# FOC_Power.net
KiCad netlist of a schematic drawn in Altium Designer
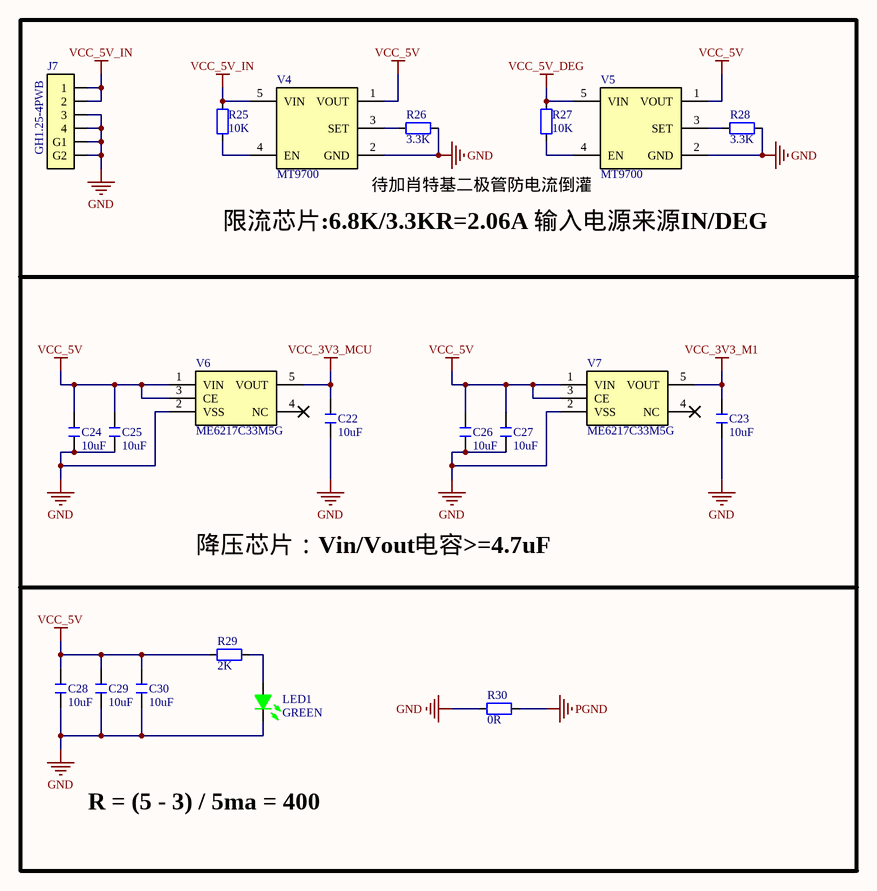
[diagram p0: FOC_Power.SchDoc]

(export (version "E")
  (design (tool "Eeschema 10.0.6"))
  (components
    (comp (ref "C22")
      (value "10uF")
      (footprint "C 0603_L")
      (description "贴片电容")
      (libsource (lib "0.1 电阻_电容_电感") (part "C"))
    )
    (comp (ref "C23")
      (value "10uF")
      (footprint "C 0603_L")
      (description "贴片电容")
      (libsource (lib "0.1 电阻_电容_电感") (part "C"))
    )
    (comp (ref "C24")
      (value "10uF")
      (footprint "C 0603_L")
      (description "贴片电容")
      (libsource (lib "0.1 电阻_电容_电感") (part "C"))
    )
    (comp (ref "C25")
      (value "10uF")
      (footprint "C 0603_L")
      (description "贴片电容")
      (libsource (lib "0.1 电阻_电容_电感") (part "C"))
    )
    (comp (ref "C26")
      (value "10uF")
      (footprint "C 0603_L")
      (description "贴片电容")
      (libsource (lib "0.1 电阻_电容_电感") (part "C"))
    )
    (comp (ref "C27")
      (value "10uF")
      (footprint "C 0603_L")
      (description "贴片电容")
      (libsource (lib "0.1 电阻_电容_电感") (part "C"))
    )
    (comp (ref "C28")
      (value "10uF")
      (footprint "C 0603_L")
      (description "贴片电容")
      (libsource (lib "0.1 电阻_电容_电感") (part "C"))
    )
    (comp (ref "C29")
      (value "10uF")
      (footprint "C 0603_L")
      (description "贴片电容")
      (libsource (lib "0.1 电阻_电容_电感") (part "C"))
    )
    (comp (ref "C30")
      (value "10uF")
      (footprint "C 0603_L")
      (description "贴片电容")
      (libsource (lib "0.1 电阻_电容_电感") (part "C"))
    )
    (comp (ref "J7")
      (value "GH1.25-4PWB")
      (footprint "GH1.25-4PWB")
      (description "GH1.25-4P 卧贴")
      (libsource (lib "3.5 连接器") (part "GH1.25-4PWB"))
    )
    (comp (ref "LED1")
      (value "GREEN")
      (footprint "LED_0603G")
      (description "贴片LED 0603 绿色")
      (libsource (lib "0.6 发光二极管") (part "LED_G"))
    )
    (comp (ref "R25")
      (value "10K")
      (footprint "R 0603_L")
      (description "贴片电阻")
      (libsource (lib "") (part "R_2"))
    )
    (comp (ref "R26")
      (value "3.3K")
      (footprint "R 0603_L")
      (description "贴片电阻")
      (libsource (lib "") (part "R_1"))
    )
    (comp (ref "R27")
      (value "10K")
      (footprint "R 0603_L")
      (description "贴片电阻")
      (libsource (lib "") (part "R_2"))
    )
    (comp (ref "R28")
      (value "3.3K")
      (footprint "R 0603_L")
      (description "贴片电阻")
      (libsource (lib "") (part "R_1"))
    )
    (comp (ref "R29")
      (value "2K")
      (footprint "R 0603_L")
      (description "贴片电阻")
      (libsource (lib "0.1 电阻_电容_电感") (part "R"))
    )
    (comp (ref "R30")
      (value "0R")
      (footprint "R 0603_L")
      (description "贴片电阻")
      (libsource (lib "0.1 电阻_电容_电感") (part "R"))
    )
    (comp (ref "V4")
      (value "MT9700")
      (footprint "SOT-23-5")
      (description "功率电子开关")
      (libsource (lib "1.2 电源芯片") (part "MT9700"))
    )
    (comp (ref "V5")
      (value "MT9700")
      (footprint "SOT-23-5")
      (description "功率电子开关")
      (libsource (lib "1.2 电源芯片") (part "MT9700"))
    )
    (comp (ref "V6")
      (value "ME6217C33M5G")
      (footprint "SOT-23-5L")
      (libsource (lib "1.2 电源芯片") (part "ME6217C33M5G"))
    )
    (comp (ref "V7")
      (value "ME6217C33M5G")
      (footprint "SOT-23-5L")
      (libsource (lib "1.2 电源芯片") (part "ME6217C33M5G"))
    )
  )
  (nets
    (net (code "1") (name "GND") (class "Default")
      (node (ref "C22") (pin "2") (pinfunction "2_2") (pintype "passive"))
      (node (ref "C23") (pin "2") (pinfunction "2_2") (pintype "passive"))
      (node (ref "C24") (pin "2") (pinfunction "2_2") (pintype "passive"))
      (node (ref "C25") (pin "2") (pinfunction "2_2") (pintype "passive"))
      (node (ref "C26") (pin "2") (pinfunction "2_2") (pintype "passive"))
      (node (ref "C27") (pin "2") (pinfunction "2_2") (pintype "passive"))
      (node (ref "C28") (pin "1") (pinfunction "1_1") (pintype "passive"))
      (node (ref "C29") (pin "2") (pinfunction "2_2") (pintype "passive"))
      (node (ref "C30") (pin "2") (pinfunction "2_2") (pintype "passive"))
      (node (ref "J7") (pin "3") (pinfunction "3_3") (pintype "passive"))
      (node (ref "J7") (pin "4") (pinfunction "4_4") (pintype "passive"))
      (node (ref "J7") (pin "G1") (pinfunction "G1_G1") (pintype "passive"))
      (node (ref "J7") (pin "G2") (pinfunction "G2_G2") (pintype "passive"))
      (node (ref "LED1") (pin "2") (pinfunction "-_2") (pintype "passive"))
      (node (ref "R26") (pin "1") (pinfunction "1_1") (pintype "passive"))
      (node (ref "R28") (pin "1") (pinfunction "1_1") (pintype "passive"))
      (node (ref "R30") (pin "1") (pinfunction "1_1") (pintype "passive"))
      (node (ref "V4") (pin "2") (pinfunction "GND_2") (pintype "passive"))
      (node (ref "V5") (pin "2") (pinfunction "GND_2") (pintype "passive"))
      (node (ref "V6") (pin "2") (pinfunction "VSS_2") (pintype "power_in"))
      (node (ref "V7") (pin "2") (pinfunction "VSS_2") (pintype "power_in"))
    )
    (net (code "2") (name "Net-(LED1-+)") (class "Default")
      (node (ref "LED1") (pin "1") (pinfunction "+_1") (pintype "passive"))
      (node (ref "R29") (pin "2") (pinfunction "2_2") (pintype "passive"))
    )
    (net (code "3") (name "Net-(V4-EN)") (class "Default")
      (node (ref "R25") (pin "1") (pinfunction "1_1") (pintype "passive"))
      (node (ref "V4") (pin "4") (pinfunction "EN_4") (pintype "passive"))
    )
    (net (code "4") (name "Net-(V4-SET)") (class "Default")
      (node (ref "R26") (pin "2") (pinfunction "2_2") (pintype "passive"))
      (node (ref "V4") (pin "3") (pinfunction "SET_3") (pintype "passive"))
    )
    (net (code "5") (name "Net-(V5-EN)") (class "Default")
      (node (ref "R27") (pin "1") (pinfunction "1_1") (pintype "passive"))
      (node (ref "V5") (pin "4") (pinfunction "EN_4") (pintype "passive"))
    )
    (net (code "6") (name "Net-(V5-SET)") (class "Default")
      (node (ref "R28") (pin "2") (pinfunction "2_2") (pintype "passive"))
      (node (ref "V5") (pin "3") (pinfunction "SET_3") (pintype "passive"))
    )
    (net (code "7") (name "PGND") (class "Default")
      (node (ref "R30") (pin "2") (pinfunction "2_2") (pintype "passive"))
    )
    (net (code "8") (name "VCC_3V3_M1") (class "Default")
      (node (ref "C23") (pin "1") (pinfunction "1_1") (pintype "passive"))
      (node (ref "V7") (pin "5") (pinfunction "VOUT_5") (pintype "power_in"))
    )
    (net (code "9") (name "VCC_3V3_MCU") (class "Default")
      (node (ref "C22") (pin "1") (pinfunction "1_1") (pintype "passive"))
      (node (ref "V6") (pin "5") (pinfunction "VOUT_5") (pintype "power_in"))
    )
    (net (code "10") (name "VCC_5V") (class "Default")
      (node (ref "C24") (pin "1") (pinfunction "1_1") (pintype "passive"))
      (node (ref "C25") (pin "1") (pinfunction "1_1") (pintype "passive"))
      (node (ref "C26") (pin "1") (pinfunction "1_1") (pintype "passive"))
      (node (ref "C27") (pin "1") (pinfunction "1_1") (pintype "passive"))
      (node (ref "C28") (pin "2") (pinfunction "2_2") (pintype "passive"))
      (node (ref "C29") (pin "1") (pinfunction "1_1") (pintype "passive"))
      (node (ref "C30") (pin "1") (pinfunction "1_1") (pintype "passive"))
      (node (ref "R29") (pin "1") (pinfunction "1_1") (pintype "passive"))
      (node (ref "V4") (pin "1") (pinfunction "VOUT_1") (pintype "passive"))
      (node (ref "V5") (pin "1") (pinfunction "VOUT_1") (pintype "passive"))
      (node (ref "V6") (pin "1") (pinfunction "VIN_1") (pintype "power_in"))
      (node (ref "V6") (pin "3") (pinfunction "CE_3") (pintype "passive"))
      (node (ref "V7") (pin "1") (pinfunction "VIN_1") (pintype "power_in"))
      (node (ref "V7") (pin "3") (pinfunction "CE_3") (pintype "passive"))
    )
    (net (code "11") (name "VCC_5V_DEG") (class "Default")
      (node (ref "R27") (pin "2") (pinfunction "2_2") (pintype "passive"))
      (node (ref "V5") (pin "5") (pinfunction "VIN_5") (pintype "passive"))
    )
    (net (code "12") (name "VCC_5V_IN") (class "Default")
      (node (ref "J7") (pin "1") (pinfunction "1_1") (pintype "passive"))
      (node (ref "J7") (pin "2") (pinfunction "2_2") (pintype "passive"))
      (node (ref "R25") (pin "2") (pinfunction "2_2") (pintype "passive"))
      (node (ref "V4") (pin "5") (pinfunction "VIN_5") (pintype "passive"))
    )
    (net (code "13") (name "unconnected-(V6-NC-Pad4)") (class "Default")
      (node (ref "V6") (pin "4") (pinfunction "NC_4") (pintype "passive+no_connect"))
    )
    (net (code "14") (name "unconnected-(V7-NC-Pad4)") (class "Default")
      (node (ref "V7") (pin "4") (pinfunction "NC_4") (pintype "passive+no_connect"))
    )
  )
)
